# QuizBuzzer.net
KiCad netlist of a schematic drawn in EAGLE
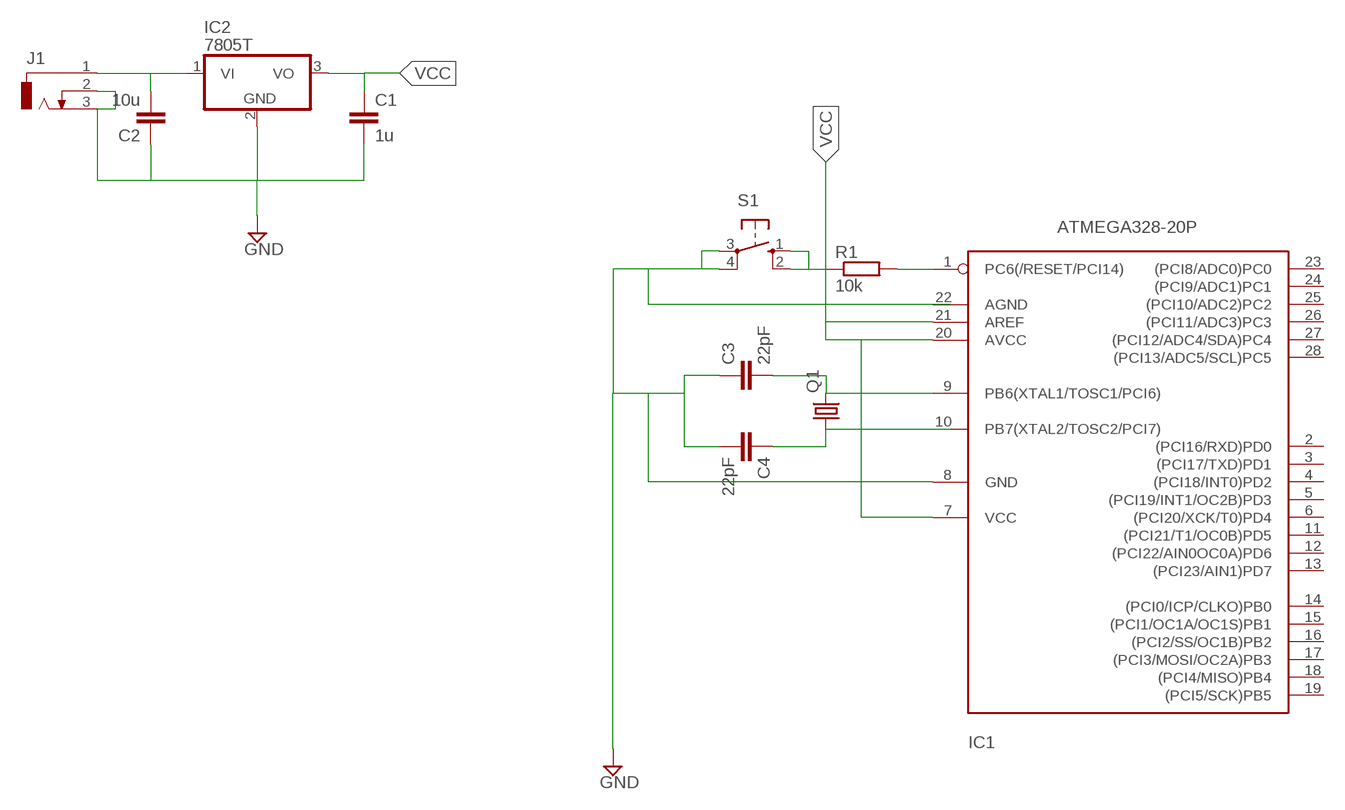
[diagram p0: schematic, sheet 1]

(export (version "E")
  (design (tool "Eeschema 10.0.6"))
  (components
    (comp (ref "C1")
      (value "1u")
      (footprint "eagle-import:C025-025X050")
      (libsource (lib "eagle-import") (part "C-EU025-025X050"))
    )
    (comp (ref "C2")
      (value "10u")
      (footprint "eagle-import:C025-025X050")
      (libsource (lib "eagle-import") (part "C-EU025-025X050"))
    )
    (comp (ref "C3")
      (value "22pF")
      (footprint "eagle-import:C025-025X050")
      (libsource (lib "eagle-import") (part "C-EU025-025X050"))
    )
    (comp (ref "C4")
      (value "22pF")
      (footprint "eagle-import:C025-025X050")
      (libsource (lib "eagle-import") (part "C-EU025-025X050"))
    )
    (comp (ref "IC1")
      (value "ATMEGA328-20P")
      (footprint "eagle-import:DIL28-3")
      (libsource (lib "eagle-import") (part "ATMEGA328P-20"))
    )
    (comp (ref "IC2")
      (value "7805T")
      (footprint "eagle-import:TO220H")
      (libsource (lib "eagle-import") (part "78T05"))
    )
    (comp (ref "J1")
      (value "DCJ0303")
      (footprint "eagle-import:DCJ0303")
      (libsource (lib "eagle-import") (part "DCJ0303"))
    )
    (comp (ref "Q1")
      (value "CRYSTALHC18U-V")
      (footprint "eagle-import:HC18U-V")
      (libsource (lib "eagle-import") (part "CRYSTALHC18U-V"))
    )
    (comp (ref "R1")
      (value "10k")
      (footprint "eagle-import:0204_7")
      (libsource (lib "eagle-import") (part "R-EU_0204/7"))
    )
    (comp (ref "S1")
      (value "10-XX")
      (footprint "eagle-import:B3F-10XX")
      (fields (field (name "MPN") "B3F-1000"))
      (libsource (lib "eagle-import") (part "10-XX"))
    )
  )
  (nets
    (net (code "1") (name "GND") (class "Default")
      (node (ref "C1") (pin "2") (pinfunction "2_2") (pintype "passive"))
      (node (ref "C2") (pin "1") (pinfunction "1_1") (pintype "passive"))
      (node (ref "C3") (pin "1") (pinfunction "1_1") (pintype "passive"))
      (node (ref "C4") (pin "2") (pinfunction "2_2") (pintype "passive"))
      (node (ref "IC1") (pin "8") (pinfunction "GND_8") (pintype "bidirectional"))
      (node (ref "IC2") (pin "2") (pinfunction "GND_2") (pintype "passive"))
      (node (ref "J1") (pin "2") (pinfunction "2_2") (pintype "passive"))
      (node (ref "J1") (pin "3") (pinfunction "3_3") (pintype "passive"))
      (node (ref "S1") (pin "3") (pinfunction "P_3") (pintype "passive"))
      (node (ref "S1") (pin "4") (pinfunction "P1_4") (pintype "passive"))
    )
    (net (code "2") (name "Net-(C4-Pad1)") (class "Default")
      (node (ref "C4") (pin "1") (pinfunction "1_1") (pintype "passive"))
      (node (ref "Q1") (pin "1") (pinfunction "1_1") (pintype "passive"))
    )
    (net (code "3") (name "Net-(IC1-PB6(XTAL1{slash}TOSC1{slash}PCI6))") (class "Default")
      (node (ref "C3") (pin "2") (pinfunction "2_2") (pintype "passive"))
      (node (ref "IC1") (pin "9") (pinfunction "PB6(XTAL1/TOSC1/PCI6)_9") (pintype "bidirectional"))
      (node (ref "Q1") (pin "2") (pinfunction "2_2") (pintype "passive"))
    )
    (net (code "4") (name "Net-(IC1-PC6({slash}RESET{slash}PCI14))") (class "Default")
      (node (ref "IC1") (pin "1") (pinfunction "PC6(/RESET/PCI14)_1") (pintype "bidirectional"))
      (node (ref "R1") (pin "2") (pinfunction "2_2") (pintype "passive"))
    )
    (net (code "5") (name "Net-(IC2-VI)") (class "Default")
      (node (ref "C2") (pin "2") (pinfunction "2_2") (pintype "passive"))
      (node (ref "IC2") (pin "1") (pinfunction "VI_1") (pintype "input"))
      (node (ref "J1") (pin "1") (pinfunction "1_1") (pintype "passive"))
    )
    (net (code "6") (name "VCC") (class "Default")
      (node (ref "C1") (pin "1") (pinfunction "1_1") (pintype "passive"))
      (node (ref "IC1") (pin "20") (pinfunction "AVCC_20") (pintype "bidirectional"))
      (node (ref "IC1") (pin "21") (pinfunction "AREF_21") (pintype "bidirectional"))
      (node (ref "IC1") (pin "7") (pinfunction "VCC_7") (pintype "bidirectional"))
      (node (ref "IC2") (pin "3") (pinfunction "VO_3") (pintype "passive"))
      (node (ref "R1") (pin "1") (pinfunction "1_1") (pintype "passive"))
      (node (ref "S1") (pin "1") (pinfunction "S_1") (pintype "passive"))
      (node (ref "S1") (pin "2") (pinfunction "S1_2") (pintype "passive"))
    )
    (net (code "7") (name "unconnected-(IC1-(PCI0{slash}ICP{slash}CLKO)PB0-Pad14)") (class "Default")
      (node (ref "IC1") (pin "14") (pinfunction "(PCI0/ICP/CLKO)PB0_14") (pintype "bidirectional"))
    )
    (net (code "8") (name "unconnected-(IC1-(PCI1{slash}OC1A{slash}OC1S)PB1-Pad15)") (class "Default")
      (node (ref "IC1") (pin "15") (pinfunction "(PCI1/OC1A/OC1S)PB1_15") (pintype "bidirectional"))
    )
    (net (code "9") (name "unconnected-(IC1-(PCI2{slash}SS{slash}OC1B)PB2-Pad16)") (class "Default")
      (node (ref "IC1") (pin "16") (pinfunction "(PCI2/SS/OC1B)PB2_16") (pintype "bidirectional"))
    )
    (net (code "10") (name "unconnected-(IC1-(PCI3{slash}MOSI{slash}OC2A)PB3-Pad17)") (class "Default")
      (node (ref "IC1") (pin "17") (pinfunction "(PCI3/MOSI/OC2A)PB3_17") (pintype "bidirectional"))
    )
    (net (code "11") (name "unconnected-(IC1-(PCI4{slash}MISO)PB4-Pad18)") (class "Default")
      (node (ref "IC1") (pin "18") (pinfunction "(PCI4/MISO)PB4_18") (pintype "bidirectional"))
    )
    (net (code "12") (name "unconnected-(IC1-(PCI5{slash}SCK)PB5-Pad19)") (class "Default")
      (node (ref "IC1") (pin "19") (pinfunction "(PCI5/SCK)PB5_19") (pintype "bidirectional"))
    )
    (net (code "13") (name "unconnected-(IC1-(PCI8{slash}ADC0)PC0-Pad23)") (class "Default")
      (node (ref "IC1") (pin "23") (pinfunction "(PCI8/ADC0)PC0_23") (pintype "bidirectional"))
    )
    (net (code "14") (name "unconnected-(IC1-(PCI9{slash}ADC1)PC1-Pad24)") (class "Default")
      (node (ref "IC1") (pin "24") (pinfunction "(PCI9/ADC1)PC1_24") (pintype "bidirectional"))
    )
    (net (code "15") (name "unconnected-(IC1-(PCI10{slash}ADC2)PC2-Pad25)") (class "Default")
      (node (ref "IC1") (pin "25") (pinfunction "(PCI10/ADC2)PC2_25") (pintype "bidirectional"))
    )
    (net (code "16") (name "unconnected-(IC1-(PCI11{slash}ADC3)PC3-Pad26)") (class "Default")
      (node (ref "IC1") (pin "26") (pinfunction "(PCI11/ADC3)PC3_26") (pintype "bidirectional"))
    )
    (net (code "17") (name "unconnected-(IC1-(PCI12{slash}ADC4{slash}SDA)PC4-Pad27)") (class "Default")
      (node (ref "IC1") (pin "27") (pinfunction "(PCI12/ADC4/SDA)PC4_27") (pintype "bidirectional"))
    )
    (net (code "18") (name "unconnected-(IC1-(PCI13{slash}ADC5{slash}SCL)PC5-Pad28)") (class "Default")
      (node (ref "IC1") (pin "28") (pinfunction "(PCI13/ADC5/SCL)PC5_28") (pintype "bidirectional"))
    )
    (net (code "19") (name "unconnected-(IC1-(PCI16{slash}RXD)PD0-Pad2)") (class "Default")
      (node (ref "IC1") (pin "2") (pinfunction "(PCI16/RXD)PD0_2") (pintype "bidirectional"))
    )
    (net (code "20") (name "unconnected-(IC1-(PCI17{slash}TXD)PD1-Pad3)") (class "Default")
      (node (ref "IC1") (pin "3") (pinfunction "(PCI17/TXD)PD1_3") (pintype "bidirectional"))
    )
    (net (code "21") (name "unconnected-(IC1-(PCI18{slash}INT0)PD2-Pad4)") (class "Default")
      (node (ref "IC1") (pin "4") (pinfunction "(PCI18/INT0)PD2_4") (pintype "bidirectional"))
    )
    (net (code "22") (name "unconnected-(IC1-(PCI19{slash}INT1{slash}OC2B)PD3-Pad5)") (class "Default")
      (node (ref "IC1") (pin "5") (pinfunction "(PCI19/INT1/OC2B)PD3_5") (pintype "bidirectional"))
    )
    (net (code "23") (name "unconnected-(IC1-(PCI20{slash}XCK{slash}T0)PD4-Pad6)") (class "Default")
      (node (ref "IC1") (pin "6") (pinfunction "(PCI20/XCK/T0)PD4_6") (pintype "bidirectional"))
    )
    (net (code "24") (name "unconnected-(IC1-(PCI21{slash}T1{slash}OC0B)PD5-Pad11)") (class "Default")
      (node (ref "IC1") (pin "11") (pinfunction "(PCI21/T1/OC0B)PD5_11") (pintype "bidirectional"))
    )
    (net (code "25") (name "unconnected-(IC1-(PCI22{slash}AIN0OC0A)PD6-Pad12)") (class "Default")
      (node (ref "IC1") (pin "12") (pinfunction "(PCI22/AIN0OC0A)PD6_12") (pintype "bidirectional"))
    )
    (net (code "26") (name "unconnected-(IC1-(PCI23{slash}AIN1)PD7-Pad13)") (class "Default")
      (node (ref "IC1") (pin "13") (pinfunction "(PCI23/AIN1)PD7_13") (pintype "bidirectional"))
    )
    (net (code "27") (name "unconnected-(IC1-AGND-Pad22)") (class "Default")
      (node (ref "IC1") (pin "22") (pinfunction "AGND_22") (pintype "bidirectional"))
    )
    (net (code "28") (name "unconnected-(IC1-PB7(XTAL2{slash}TOSC2{slash}PCI7)-Pad10)") (class "Default")
      (node (ref "IC1") (pin "10") (pinfunction "PB7(XTAL2/TOSC2/PCI7)_10") (pintype "bidirectional"))
    )
  )
)
